# v2_4_button.net
KiCad netlist of a schematic drawn in EAGLE
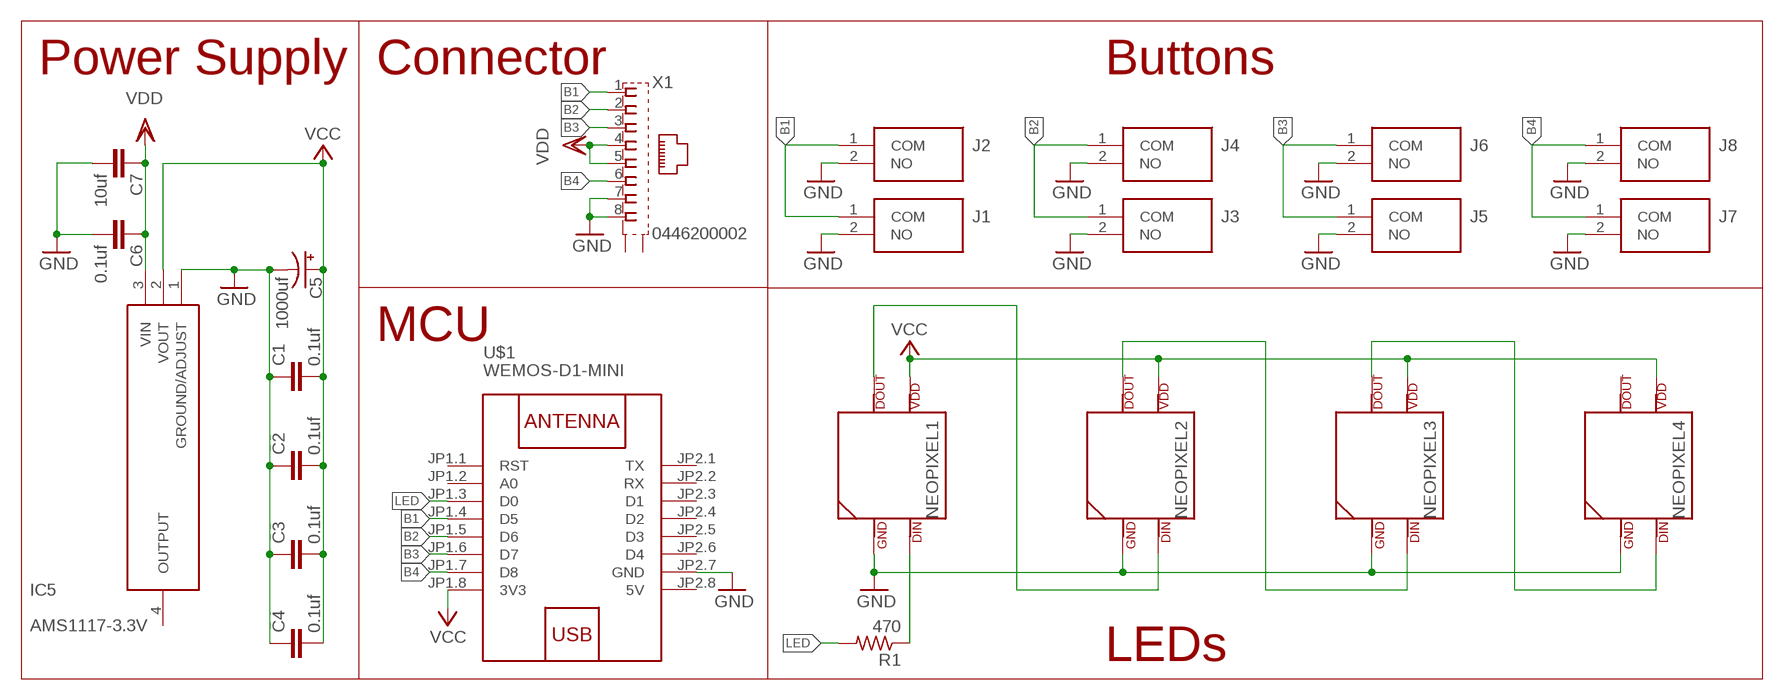
[diagram p0: schematic, sheet 1]

(export (version "E")
  (design (tool "Eeschema 10.0.6"))
  (components
    (comp (ref "C1")
      (value "0.1uf")
      (footprint "eagle-import:C0603")
      (libsource (lib "eagle-import") (part "C-EUC0603"))
    )
    (comp (ref "C2")
      (value "0.1uf")
      (footprint "eagle-import:C0603")
      (libsource (lib "eagle-import") (part "C-EUC0603"))
    )
    (comp (ref "C3")
      (value "0.1uf")
      (footprint "eagle-import:C0603")
      (libsource (lib "eagle-import") (part "C-EUC0603"))
    )
    (comp (ref "C4")
      (value "0.1uf")
      (footprint "eagle-import:C0603")
      (libsource (lib "eagle-import") (part "C-EUC0603"))
    )
    (comp (ref "C5")
      (value "1000uf")
      (footprint "eagle-import:UD-10X10_NICHICON")
      (libsource (lib "eagle-import") (part "CPOL-USUD-10X10"))
    )
    (comp (ref "C6")
      (value "0.1uf")
      (footprint "eagle-import:C0603")
      (libsource (lib "eagle-import") (part "C-EUC0603"))
    )
    (comp (ref "C7")
      (value "10uf")
      (footprint "eagle-import:C0603")
      (libsource (lib "eagle-import") (part "C-EUC0603"))
    )
    (comp (ref "IC5")
      (value "AMS1117-3.3V")
      (footprint "eagle-import:SOT229P700X180-4N")
      (fields (field (name "MANUFACTURER_PART_NUMBER") "ams1117-3.3v"))
      (libsource (lib "eagle-import") (part "AMS1117-3.3V"))
    )
    (comp (ref "J1")
      (value "PTS636_SM25F_SMTR_LFS")
      (footprint "eagle-import:PTS636SM25FSMTRLFS")
      (fields
        (field (name "ARROW_PART_NUMBER") "PTS636 SM25F SMTR LFS")
        (field (name "MOUSER_PART_NUMBER") "611-PTS636SM25FSMTRL")
      )
      (libsource (lib "eagle-import") (part "PTS636_SM25F_SMTR_LFS"))
    )
    (comp (ref "J2")
      (value "PTS636_SM25F_SMTR_LFS")
      (footprint "eagle-import:PTS636SM25FSMTRLFS")
      (fields
        (field (name "ARROW_PART_NUMBER") "PTS636 SM25F SMTR LFS")
        (field (name "MOUSER_PART_NUMBER") "611-PTS636SM25FSMTRL")
      )
      (libsource (lib "eagle-import") (part "PTS636_SM25F_SMTR_LFS"))
    )
    (comp (ref "J3")
      (value "PTS636_SM25F_SMTR_LFS")
      (footprint "eagle-import:PTS636SM25FSMTRLFS")
      (fields
        (field (name "ARROW_PART_NUMBER") "PTS636 SM25F SMTR LFS")
        (field (name "MOUSER_PART_NUMBER") "611-PTS636SM25FSMTRL")
      )
      (libsource (lib "eagle-import") (part "PTS636_SM25F_SMTR_LFS"))
    )
    (comp (ref "J4")
      (value "PTS636_SM25F_SMTR_LFS")
      (footprint "eagle-import:PTS636SM25FSMTRLFS")
      (fields
        (field (name "ARROW_PART_NUMBER") "PTS636 SM25F SMTR LFS")
        (field (name "MOUSER_PART_NUMBER") "611-PTS636SM25FSMTRL")
      )
      (libsource (lib "eagle-import") (part "PTS636_SM25F_SMTR_LFS"))
    )
    (comp (ref "J5")
      (value "PTS636_SM25F_SMTR_LFS")
      (footprint "eagle-import:PTS636SM25FSMTRLFS")
      (fields
        (field (name "ARROW_PART_NUMBER") "PTS636 SM25F SMTR LFS")
        (field (name "MOUSER_PART_NUMBER") "611-PTS636SM25FSMTRL")
      )
      (libsource (lib "eagle-import") (part "PTS636_SM25F_SMTR_LFS"))
    )
    (comp (ref "J6")
      (value "PTS636_SM25F_SMTR_LFS")
      (footprint "eagle-import:PTS636SM25FSMTRLFS")
      (fields
        (field (name "ARROW_PART_NUMBER") "PTS636 SM25F SMTR LFS")
        (field (name "MOUSER_PART_NUMBER") "611-PTS636SM25FSMTRL")
      )
      (libsource (lib "eagle-import") (part "PTS636_SM25F_SMTR_LFS"))
    )
    (comp (ref "J7")
      (value "PTS636_SM25F_SMTR_LFS")
      (footprint "eagle-import:PTS636SM25FSMTRLFS")
      (fields
        (field (name "ARROW_PART_NUMBER") "PTS636 SM25F SMTR LFS")
        (field (name "MOUSER_PART_NUMBER") "611-PTS636SM25FSMTRL")
      )
      (libsource (lib "eagle-import") (part "PTS636_SM25F_SMTR_LFS"))
    )
    (comp (ref "J8")
      (value "PTS636_SM25F_SMTR_LFS")
      (footprint "eagle-import:PTS636SM25FSMTRLFS")
      (fields
        (field (name "ARROW_PART_NUMBER") "PTS636 SM25F SMTR LFS")
        (field (name "MOUSER_PART_NUMBER") "611-PTS636SM25FSMTRL")
      )
      (libsource (lib "eagle-import") (part "PTS636_SM25F_SMTR_LFS"))
    )
    (comp (ref "NEOPIXEL1")
      (value "SK6812NEOPIXEL5050")
      (footprint "eagle-import:SK6812")
      (libsource (lib "eagle-import") (part "SK68125050NEOPIXEL"))
    )
    (comp (ref "NEOPIXEL2")
      (value "SK6812NEOPIXEL5050")
      (footprint "eagle-import:SK6812")
      (libsource (lib "eagle-import") (part "SK68125050NEOPIXEL"))
    )
    (comp (ref "NEOPIXEL3")
      (value "SK6812NEOPIXEL5050")
      (footprint "eagle-import:SK6812")
      (libsource (lib "eagle-import") (part "SK68125050NEOPIXEL"))
    )
    (comp (ref "NEOPIXEL4")
      (value "SK6812NEOPIXEL5050")
      (footprint "eagle-import:SK6812")
      (libsource (lib "eagle-import") (part "SK68125050NEOPIXEL"))
    )
    (comp (ref "R1")
      (value "470")
      (footprint "eagle-import:R0603")
      (libsource (lib "eagle-import") (part "R-US_R0603"))
    )
    (comp (ref "U$1")
      (value "WEMOS-D1-MINI")
      (footprint "eagle-import:WEMOS-D1-MINI")
      (libsource (lib "eagle-import") (part "WEMOS-D1-MINI"))
    )
    (comp (ref "X1")
      (value "0446200002")
      (footprint "eagle-import:0446200002")
      (fields (field (name "MF") "MOLEX"))
      (libsource (lib "eagle-import") (part "0446200002"))
    )
  )
  (nets
    (net (code "1") (name "/5V") (class "Default")
      (node (ref "U$1") (pin "JP2.8") (pinfunction "5V_JP2.8") (pintype "power_in"))
    )
    (net (code "2") (name "B1") (class "Default")
      (node (ref "J1") (pin "1") (pinfunction "COM_1") (pintype "bidirectional"))
      (node (ref "J2") (pin "1") (pinfunction "COM_1") (pintype "bidirectional"))
      (node (ref "U$1") (pin "JP1.4") (pinfunction "D5_JP1.4") (pintype "bidirectional"))
      (node (ref "X1") (pin "1") (pinfunction "1_1") (pintype "passive"))
    )
    (net (code "3") (name "B2") (class "Default")
      (node (ref "J3") (pin "1") (pinfunction "COM_1") (pintype "bidirectional"))
      (node (ref "J4") (pin "1") (pinfunction "COM_1") (pintype "bidirectional"))
      (node (ref "U$1") (pin "JP1.5") (pinfunction "D6_JP1.5") (pintype "bidirectional"))
      (node (ref "X1") (pin "2") (pinfunction "2_2") (pintype "passive"))
    )
    (net (code "4") (name "B3") (class "Default")
      (node (ref "J5") (pin "1") (pinfunction "COM_1") (pintype "bidirectional"))
      (node (ref "J6") (pin "1") (pinfunction "COM_1") (pintype "bidirectional"))
      (node (ref "U$1") (pin "JP1.6") (pinfunction "D7_JP1.6") (pintype "bidirectional"))
      (node (ref "X1") (pin "3") (pinfunction "3_3") (pintype "passive"))
    )
    (net (code "5") (name "B4") (class "Default")
      (node (ref "J7") (pin "1") (pinfunction "COM_1") (pintype "bidirectional"))
      (node (ref "J8") (pin "1") (pinfunction "COM_1") (pintype "bidirectional"))
      (node (ref "U$1") (pin "JP1.7") (pinfunction "D8_JP1.7") (pintype "bidirectional"))
      (node (ref "X1") (pin "6") (pinfunction "6_6") (pintype "passive"))
    )
    (net (code "6") (name "GND") (class "Default")
      (node (ref "C1") (pin "1") (pinfunction "1_1") (pintype "passive"))
      (node (ref "C2") (pin "1") (pinfunction "1_1") (pintype "passive"))
      (node (ref "C3") (pin "1") (pinfunction "1_1") (pintype "passive"))
      (node (ref "C4") (pin "1") (pinfunction "1_1") (pintype "passive"))
      (node (ref "C5") (pin "-") (pinfunction "-_-") (pintype "passive"))
      (node (ref "C6") (pin "2") (pinfunction "2_2") (pintype "passive"))
      (node (ref "C7") (pin "2") (pinfunction "2_2") (pintype "passive"))
      (node (ref "IC5") (pin "1") (pinfunction "GROUND/ADJUST_1") (pintype "bidirectional"))
      (node (ref "J1") (pin "2") (pinfunction "NO_2") (pintype "bidirectional"))
      (node (ref "J2") (pin "2") (pinfunction "NO_2") (pintype "bidirectional"))
      (node (ref "J3") (pin "2") (pinfunction "NO_2") (pintype "bidirectional"))
      (node (ref "J4") (pin "2") (pinfunction "NO_2") (pintype "bidirectional"))
      (node (ref "J5") (pin "2") (pinfunction "NO_2") (pintype "bidirectional"))
      (node (ref "J6") (pin "2") (pinfunction "NO_2") (pintype "bidirectional"))
      (node (ref "J7") (pin "2") (pinfunction "NO_2") (pintype "bidirectional"))
      (node (ref "J8") (pin "2") (pinfunction "NO_2") (pintype "bidirectional"))
      (node (ref "NEOPIXEL1") (pin "3") (pinfunction "GND_3") (pintype "bidirectional"))
      (node (ref "NEOPIXEL2") (pin "3") (pinfunction "GND_3") (pintype "bidirectional"))
      (node (ref "NEOPIXEL3") (pin "3") (pinfunction "GND_3") (pintype "bidirectional"))
      (node (ref "NEOPIXEL4") (pin "3") (pinfunction "GND_3") (pintype "bidirectional"))
      (node (ref "U$1") (pin "JP2.7") (pinfunction "GND_JP2.7") (pintype "power_in"))
      (node (ref "X1") (pin "7") (pinfunction "7_7") (pintype "passive"))
      (node (ref "X1") (pin "8") (pinfunction "8_8") (pintype "passive"))
    )
    (net (code "7") (name "LED") (class "Default")
      (node (ref "R1") (pin "2") (pinfunction "2_2") (pintype "passive"))
      (node (ref "U$1") (pin "JP1.3") (pinfunction "D0_JP1.3") (pintype "bidirectional"))
    )
    (net (code "8") (name "Net-(NEOPIXEL1-DIN)") (class "Default")
      (node (ref "NEOPIXEL1") (pin "4") (pinfunction "DIN_4") (pintype "bidirectional"))
      (node (ref "R1") (pin "1") (pinfunction "1_1") (pintype "passive"))
    )
    (net (code "9") (name "Net-(NEOPIXEL1-DOUT)") (class "Default")
      (node (ref "NEOPIXEL1") (pin "2") (pinfunction "DOUT_2") (pintype "bidirectional"))
      (node (ref "NEOPIXEL2") (pin "4") (pinfunction "DIN_4") (pintype "bidirectional"))
    )
    (net (code "10") (name "Net-(NEOPIXEL2-DOUT)") (class "Default")
      (node (ref "NEOPIXEL2") (pin "2") (pinfunction "DOUT_2") (pintype "bidirectional"))
      (node (ref "NEOPIXEL3") (pin "4") (pinfunction "DIN_4") (pintype "bidirectional"))
    )
    (net (code "11") (name "Net-(NEOPIXEL3-DOUT)") (class "Default")
      (node (ref "NEOPIXEL3") (pin "2") (pinfunction "DOUT_2") (pintype "bidirectional"))
      (node (ref "NEOPIXEL4") (pin "4") (pinfunction "DIN_4") (pintype "bidirectional"))
    )
    (net (code "12") (name "VCC") (class "Default")
      (node (ref "C1") (pin "2") (pinfunction "2_2") (pintype "passive"))
      (node (ref "C2") (pin "2") (pinfunction "2_2") (pintype "passive"))
      (node (ref "C3") (pin "2") (pinfunction "2_2") (pintype "passive"))
      (node (ref "C4") (pin "2") (pinfunction "2_2") (pintype "passive"))
      (node (ref "C5") (pin "+") (pinfunction "+_+") (pintype "passive"))
      (node (ref "IC5") (pin "2") (pinfunction "VOUT_2") (pintype "bidirectional"))
      (node (ref "NEOPIXEL1") (pin "1") (pinfunction "VDD_1") (pintype "bidirectional"))
      (node (ref "NEOPIXEL2") (pin "1") (pinfunction "VDD_1") (pintype "bidirectional"))
      (node (ref "NEOPIXEL3") (pin "1") (pinfunction "VDD_1") (pintype "bidirectional"))
      (node (ref "NEOPIXEL4") (pin "1") (pinfunction "VDD_1") (pintype "bidirectional"))
      (node (ref "U$1") (pin "JP1.8") (pinfunction "3V3_JP1.8") (pintype "power_in"))
    )
    (net (code "13") (name "VDD") (class "Default")
      (node (ref "C6") (pin "1") (pinfunction "1_1") (pintype "passive"))
      (node (ref "C7") (pin "1") (pinfunction "1_1") (pintype "passive"))
      (node (ref "IC5") (pin "3") (pinfunction "VIN_3") (pintype "bidirectional"))
      (node (ref "X1") (pin "4") (pinfunction "4_4") (pintype "passive"))
      (node (ref "X1") (pin "5") (pinfunction "5_5") (pintype "passive"))
    )
    (net (code "14") (name "unconnected-(IC5-OUTPUT-Pad4)") (class "Default")
      (node (ref "IC5") (pin "4") (pinfunction "OUTPUT_4") (pintype "bidirectional"))
    )
    (net (code "15") (name "unconnected-(NEOPIXEL4-DOUT-Pad2)") (class "Default")
      (node (ref "NEOPIXEL4") (pin "2") (pinfunction "DOUT_2") (pintype "bidirectional"))
    )
    (net (code "16") (name "unconnected-(U$1-A0-PadJP1.2)") (class "Default")
      (node (ref "U$1") (pin "JP1.2") (pinfunction "A0_JP1.2") (pintype "bidirectional"))
    )
    (net (code "17") (name "unconnected-(U$1-D1-PadJP2.3)") (class "Default")
      (node (ref "U$1") (pin "JP2.3") (pinfunction "D1_JP2.3") (pintype "bidirectional"))
    )
    (net (code "18") (name "unconnected-(U$1-D2-PadJP2.4)") (class "Default")
      (node (ref "U$1") (pin "JP2.4") (pinfunction "D2_JP2.4") (pintype "bidirectional"))
    )
    (net (code "19") (name "unconnected-(U$1-D3-PadJP2.5)") (class "Default")
      (node (ref "U$1") (pin "JP2.5") (pinfunction "D3_JP2.5") (pintype "bidirectional"))
    )
    (net (code "20") (name "unconnected-(U$1-D4-PadJP2.6)") (class "Default")
      (node (ref "U$1") (pin "JP2.6") (pinfunction "D4_JP2.6") (pintype "bidirectional"))
    )
    (net (code "21") (name "unconnected-(U$1-RST-PadJP1.1)") (class "Default")
      (node (ref "U$1") (pin "JP1.1") (pinfunction "RST_JP1.1") (pintype "bidirectional"))
    )
    (net (code "22") (name "unconnected-(U$1-RX-PadJP2.2)") (class "Default")
      (node (ref "U$1") (pin "JP2.2") (pinfunction "RX_JP2.2") (pintype "bidirectional"))
    )
    (net (code "23") (name "unconnected-(U$1-TX-PadJP2.1)") (class "Default")
      (node (ref "U$1") (pin "JP2.1") (pinfunction "TX_JP2.1") (pintype "bidirectional"))
    )
    (net (code "24") (name "unconnected-(X1-S1-PadS@1)") (class "Default")
      (node (ref "X1") (pin "S@1") (pinfunction "S1_S@1") (pintype "passive"))
    )
    (net (code "25") (name "unconnected-(X1-S2-PadS@2)") (class "Default")
      (node (ref "X1") (pin "S@2") (pinfunction "S2_S@2") (pintype "passive"))
    )
  )
)
